# Clock2_1.net
KiCad netlist of a schematic drawn in EAGLE
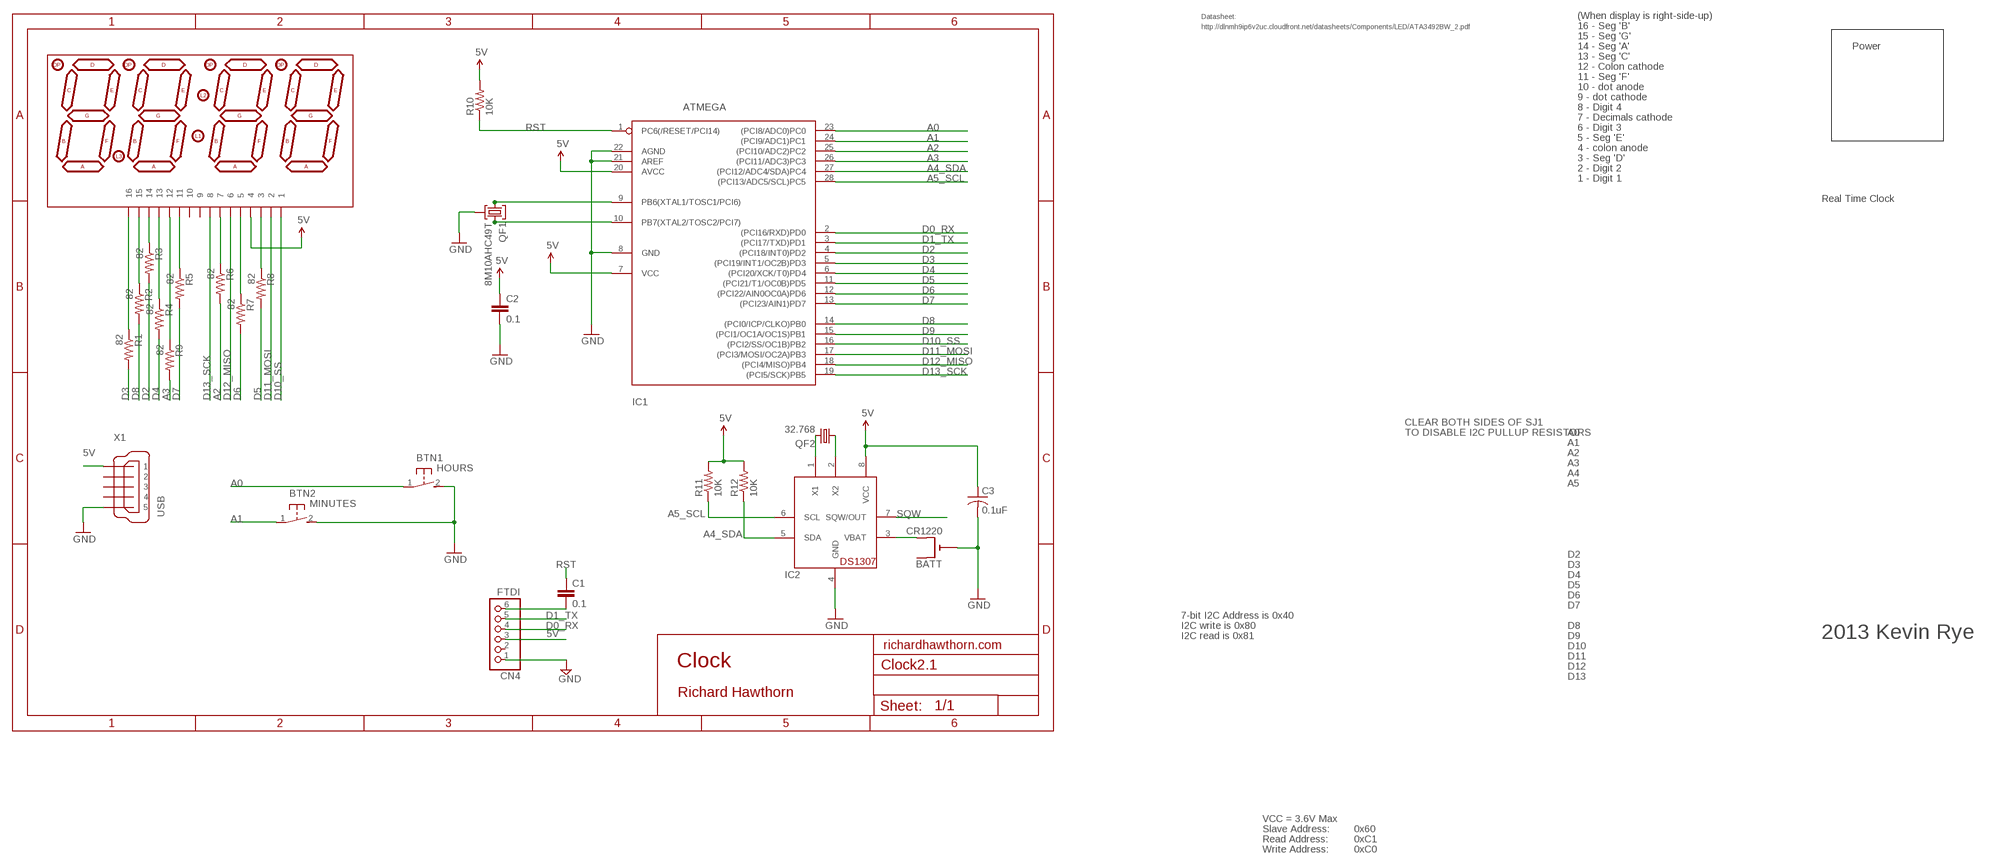
[diagram p0: schematic, sheet 1]

(export (version "E")
  (design (tool "Eeschema 10.0.6"))
  (components
    (comp (ref "BATT")
      (value "CR1220")
      (footprint "eagle-import:CR1220-SMD")
      (libsource (lib "eagle-import") (part "CR1220SMT"))
    )
    (comp (ref "BTN1")
      (value "HOURS")
      (footprint "eagle-import:DTS-3")
      (libsource (lib "eagle-import") (part "DTS-3"))
    )
    (comp (ref "BTN2")
      (value "MINUTES")
      (footprint "eagle-import:DTS-3")
      (libsource (lib "eagle-import") (part "DTS-3"))
    )
    (comp (ref "C1")
      (value "0.1")
      (footprint "eagle-import:CAP-PTH-SMALL2")
      (libsource (lib "eagle-import") (part "CAPPTH2"))
    )
    (comp (ref "C2")
      (value "0.1")
      (footprint "eagle-import:CAP-PTH-SMALL2")
      (libsource (lib "eagle-import") (part "CAPPTH2"))
    )
    (comp (ref "C3")
      (value "0.1uF")
      (footprint "eagle-import:C025-025X050")
      (libsource (lib "eagle-import") (part "C-US025-025X050"))
    )
    (comp (ref "CN4")
      (value "FTDI")
      (footprint "eagle-import:1X06")
      (libsource (lib "eagle-import") (part "PINHD-1X6"))
    )
    (comp (ref "IC1")
      (value "ATMEGA")
      (footprint "eagle-import:DIL28-3-ROUND")
      (libsource (lib "eagle-import") (part "ATMEGA168PROUND"))
    )
    (comp (ref "IC2")
      (value "DS1307")
      (footprint "eagle-import:DIL08")
      (libsource (lib "eagle-import") (part "DS1307"))
    )
    (comp (ref "LED1")
      (value "7SEG-4DIGIT")
      (footprint "eagle-import:SPARKFUN_7-SEGMENT-4DIGIT")
      (libsource (lib "eagle-import") (part "7SEG-4DIGIT"))
    )
    (comp (ref "QF1")
      (value "8M10AHC49T")
      (footprint "eagle-import:HC49U")
      (libsource (lib "eagle-import") (part "8M10AHC49T"))
    )
    (comp (ref "QF2")
      (value "32.768")
      (footprint "eagle-import:TC38H")
      (libsource (lib "eagle-import") (part "CRYTALTC38H"))
    )
    (comp (ref "R1")
      (value "82")
      (footprint "eagle-import:0204_7")
      (libsource (lib "eagle-import") (part "R-US_0204/7"))
    )
    (comp (ref "R2")
      (value "82")
      (footprint "eagle-import:0204_7")
      (libsource (lib "eagle-import") (part "R-US_0204/7"))
    )
    (comp (ref "R3")
      (value "82")
      (footprint "eagle-import:0204_7")
      (libsource (lib "eagle-import") (part "R-US_0204/7"))
    )
    (comp (ref "R4")
      (value "82")
      (footprint "eagle-import:0204_7")
      (libsource (lib "eagle-import") (part "R-US_0204/7"))
    )
    (comp (ref "R5")
      (value "82")
      (footprint "eagle-import:0204_7")
      (libsource (lib "eagle-import") (part "R-US_0204/7"))
    )
    (comp (ref "R6")
      (value "82")
      (footprint "eagle-import:0204_7")
      (libsource (lib "eagle-import") (part "R-US_0204/7"))
    )
    (comp (ref "R7")
      (value "82")
      (footprint "eagle-import:0204_7")
      (libsource (lib "eagle-import") (part "R-US_0204/7"))
    )
    (comp (ref "R8")
      (value "82")
      (footprint "eagle-import:0204_7")
      (libsource (lib "eagle-import") (part "R-US_0204/7"))
    )
    (comp (ref "R9")
      (value "82")
      (footprint "eagle-import:0204_7")
      (libsource (lib "eagle-import") (part "R-US_0204/7"))
    )
    (comp (ref "R10")
      (value "10K")
      (footprint "eagle-import:0204_7")
      (libsource (lib "eagle-import") (part "R-US_0204/7"))
    )
    (comp (ref "R11")
      (value "10K")
      (footprint "eagle-import:0204_7")
      (libsource (lib "eagle-import") (part "R-US_0204/7"))
    )
    (comp (ref "R12")
      (value "10K")
      (footprint "eagle-import:0204_7")
      (libsource (lib "eagle-import") (part "R-US_0204/7"))
    )
    (comp (ref "X1")
      (value "USB")
      (footprint "eagle-import:32005-601")
      (libsource (lib "eagle-import") (part "MINI-USB_SHIELD5P2-32005-601"))
    )
  )
  (nets
    (net (code "1") (name "/A0") (class "Default")
      (node (ref "BTN1") (pin "1") (pinfunction "1_1") (pintype "passive"))
      (node (ref "IC1") (pin "23") (pinfunction "(PCI8/ADC0)PC0_23") (pintype "bidirectional"))
    )
    (net (code "2") (name "/A1") (class "Default")
      (node (ref "BTN2") (pin "1") (pinfunction "1_1") (pintype "passive"))
      (node (ref "IC1") (pin "24") (pinfunction "(PCI9/ADC1)PC1_24") (pintype "bidirectional"))
    )
    (net (code "3") (name "/A2") (class "Default")
      (node (ref "IC1") (pin "25") (pinfunction "(PCI10/ADC2)PC2_25") (pintype "bidirectional"))
      (node (ref "R6") (pin "2") (pinfunction "2_2") (pintype "passive"))
    )
    (net (code "4") (name "/A3") (class "Default")
      (node (ref "IC1") (pin "26") (pinfunction "(PCI11/ADC3)PC3_26") (pintype "bidirectional"))
      (node (ref "R9") (pin "2") (pinfunction "2_2") (pintype "passive"))
    )
    (net (code "5") (name "/A4_SDA") (class "Default")
      (node (ref "IC1") (pin "27") (pinfunction "(PCI12/ADC4/SDA)PC4_27") (pintype "bidirectional"))
      (node (ref "IC2") (pin "5") (pinfunction "SDA_5") (pintype "bidirectional"))
      (node (ref "R12") (pin "1") (pinfunction "1_1") (pintype "passive"))
    )
    (net (code "6") (name "/A5_SCL") (class "Default")
      (node (ref "IC1") (pin "28") (pinfunction "(PCI13/ADC5/SCL)PC5_28") (pintype "bidirectional"))
      (node (ref "IC2") (pin "6") (pinfunction "SCL_6") (pintype "bidirectional"))
      (node (ref "R11") (pin "1") (pinfunction "1_1") (pintype "passive"))
    )
    (net (code "7") (name "/D0_RX") (class "Default")
      (node (ref "CN4") (pin "4") (pinfunction "4_4") (pintype "passive"))
      (node (ref "IC1") (pin "2") (pinfunction "(PCI16/RXD)PD0_2") (pintype "bidirectional"))
    )
    (net (code "8") (name "/D1_TX") (class "Default")
      (node (ref "CN4") (pin "5") (pinfunction "5_5") (pintype "passive"))
      (node (ref "IC1") (pin "3") (pinfunction "(PCI17/TXD)PD1_3") (pintype "bidirectional"))
    )
    (net (code "9") (name "/D2") (class "Default")
      (node (ref "IC1") (pin "4") (pinfunction "(PCI18/INT0)PD2_4") (pintype "bidirectional"))
      (node (ref "R3") (pin "2") (pinfunction "2_2") (pintype "passive"))
    )
    (net (code "10") (name "/D3") (class "Default")
      (node (ref "IC1") (pin "5") (pinfunction "(PCI19/INT1/OC2B)PD3_5") (pintype "bidirectional"))
      (node (ref "R1") (pin "2") (pinfunction "2_2") (pintype "passive"))
    )
    (net (code "11") (name "/D4") (class "Default")
      (node (ref "IC1") (pin "6") (pinfunction "(PCI20/XCK/T0)PD4_6") (pintype "bidirectional"))
      (node (ref "R4") (pin "2") (pinfunction "2_2") (pintype "passive"))
    )
    (net (code "12") (name "/D5") (class "Default")
      (node (ref "IC1") (pin "11") (pinfunction "(PCI21/T1/OC0B)PD5_11") (pintype "bidirectional"))
      (node (ref "R8") (pin "2") (pinfunction "2_2") (pintype "passive"))
    )
    (net (code "13") (name "/D6") (class "Default")
      (node (ref "IC1") (pin "12") (pinfunction "(PCI22/AIN0OC0A)PD6_12") (pintype "bidirectional"))
      (node (ref "R7") (pin "2") (pinfunction "2_2") (pintype "passive"))
    )
    (net (code "14") (name "/D7") (class "Default")
      (node (ref "IC1") (pin "13") (pinfunction "(PCI23/AIN1)PD7_13") (pintype "bidirectional"))
      (node (ref "R5") (pin "2") (pinfunction "2_2") (pintype "passive"))
    )
    (net (code "15") (name "/D8") (class "Default")
      (node (ref "IC1") (pin "14") (pinfunction "(PCI0/ICP/CLKO)PB0_14") (pintype "bidirectional"))
      (node (ref "R2") (pin "2") (pinfunction "2_2") (pintype "passive"))
    )
    (net (code "16") (name "/D9") (class "Default")
      (node (ref "IC1") (pin "15") (pinfunction "(PCI1/OC1A/OC1S)PB1_15") (pintype "bidirectional"))
    )
    (net (code "17") (name "/D10_SS") (class "Default")
      (node (ref "IC1") (pin "16") (pinfunction "(PCI2/SS/OC1B)PB2_16") (pintype "bidirectional"))
      (node (ref "LED1") (pin "1") (pinfunction "1_1") (pintype "bidirectional"))
    )
    (net (code "18") (name "/D11_MOSI") (class "Default")
      (node (ref "IC1") (pin "17") (pinfunction "(PCI3/MOSI/OC2A)PB3_17") (pintype "bidirectional"))
      (node (ref "LED1") (pin "2") (pinfunction "2_2") (pintype "bidirectional"))
    )
    (net (code "19") (name "/D12_MISO") (class "Default")
      (node (ref "IC1") (pin "18") (pinfunction "(PCI4/MISO)PB4_18") (pintype "bidirectional"))
      (node (ref "LED1") (pin "6") (pinfunction "6_6") (pintype "bidirectional"))
    )
    (net (code "20") (name "/D13_SCK") (class "Default")
      (node (ref "IC1") (pin "19") (pinfunction "(PCI5/SCK)PB5_19") (pintype "bidirectional"))
      (node (ref "LED1") (pin "8") (pinfunction "8_8") (pintype "bidirectional"))
    )
    (net (code "21") (name "/RST") (class "Default")
      (node (ref "C1") (pin "1") (pinfunction "1_1") (pintype "passive"))
      (node (ref "IC1") (pin "1") (pinfunction "PC6(/RESET/PCI14)_1") (pintype "bidirectional"))
      (node (ref "R10") (pin "1") (pinfunction "1_1") (pintype "passive"))
    )
    (net (code "22") (name "/SQW") (class "Default")
      (node (ref "IC2") (pin "7") (pinfunction "SQW/OUT_7") (pintype "bidirectional"))
    )
    (net (code "23") (name "5V") (class "Default")
      (node (ref "C2") (pin "1") (pinfunction "1_1") (pintype "passive"))
      (node (ref "C3") (pin "1") (pinfunction "1_1") (pintype "passive"))
      (node (ref "CN4") (pin "3") (pinfunction "3_3") (pintype "passive"))
      (node (ref "IC1") (pin "20") (pinfunction "AVCC_20") (pintype "bidirectional"))
      (node (ref "IC1") (pin "7") (pinfunction "VCC_7") (pintype "bidirectional"))
      (node (ref "IC2") (pin "8") (pinfunction "VCC_8") (pintype "power_in"))
      (node (ref "LED1") (pin "4") (pinfunction "4_4") (pintype "bidirectional"))
      (node (ref "R10") (pin "2") (pinfunction "2_2") (pintype "passive"))
      (node (ref "R11") (pin "2") (pinfunction "2_2") (pintype "passive"))
      (node (ref "R12") (pin "2") (pinfunction "2_2") (pintype "passive"))
      (node (ref "X1") (pin "1") (pinfunction "1_1") (pintype "passive"))
    )
    (net (code "24") (name "GND") (class "Default")
      (node (ref "BATT") (pin "-") (pinfunction "-_-") (pintype "passive"))
      (node (ref "BTN1") (pin "2") (pinfunction "2_2") (pintype "passive"))
      (node (ref "BTN2") (pin "2") (pinfunction "2_2") (pintype "passive"))
      (node (ref "C2") (pin "2") (pinfunction "2_2") (pintype "passive"))
      (node (ref "C3") (pin "2") (pinfunction "2_2") (pintype "passive"))
      (node (ref "CN4") (pin "1") (pinfunction "1_1") (pintype "passive"))
      (node (ref "IC1") (pin "21") (pinfunction "AREF_21") (pintype "bidirectional"))
      (node (ref "IC1") (pin "22") (pinfunction "AGND_22") (pintype "bidirectional"))
      (node (ref "IC1") (pin "8") (pinfunction "GND_8") (pintype "bidirectional"))
      (node (ref "IC2") (pin "4") (pinfunction "GND_4") (pintype "power_in"))
      (node (ref "QF1") (pin "2") (pinfunction "2_2") (pintype "passive"))
      (node (ref "X1") (pin "5") (pinfunction "5_5") (pintype "passive"))
    )
    (net (code "25") (name "Net-(BATT-+1)") (class "Default")
      (node (ref "BATT") (pin "+$2") (pinfunction "+1_+$2") (pintype "passive"))
      (node (ref "IC2") (pin "3") (pinfunction "VBAT_3") (pintype "power_in"))
    )
    (net (code "26") (name "Net-(C1-Pad2)") (class "Default")
      (node (ref "C1") (pin "2") (pinfunction "2_2") (pintype "passive"))
      (node (ref "CN4") (pin "6") (pinfunction "6_6") (pintype "passive"))
    )
    (net (code "27") (name "Net-(IC1-PB6(XTAL1{slash}TOSC1{slash}PCI6))") (class "Default")
      (node (ref "IC1") (pin "9") (pinfunction "PB6(XTAL1/TOSC1/PCI6)_9") (pintype "bidirectional"))
      (node (ref "QF1") (pin "1") (pinfunction "1_1") (pintype "passive"))
    )
    (net (code "28") (name "Net-(IC1-PB7(XTAL2{slash}TOSC2{slash}PCI7))") (class "Default")
      (node (ref "IC1") (pin "10") (pinfunction "PB7(XTAL2/TOSC2/PCI7)_10") (pintype "bidirectional"))
      (node (ref "QF1") (pin "3") (pinfunction "3_3") (pintype "passive"))
    )
    (net (code "29") (name "Net-(IC2-X1)") (class "Default")
      (node (ref "IC2") (pin "1") (pinfunction "X1_1") (pintype "passive"))
      (node (ref "QF2") (pin "2") (pinfunction "2_2") (pintype "passive"))
    )
    (net (code "30") (name "Net-(IC2-X2)") (class "Default")
      (node (ref "IC2") (pin "2") (pinfunction "X2_2") (pintype "passive"))
      (node (ref "QF2") (pin "1") (pinfunction "1_1") (pintype "passive"))
    )
    (net (code "31") (name "Net-(LED1-Pad3)") (class "Default")
      (node (ref "LED1") (pin "3") (pinfunction "3_3") (pintype "bidirectional"))
      (node (ref "R8") (pin "1") (pinfunction "1_1") (pintype "passive"))
    )
    (net (code "32") (name "Net-(LED1-Pad5)") (class "Default")
      (node (ref "LED1") (pin "5") (pinfunction "5_5") (pintype "bidirectional"))
      (node (ref "R7") (pin "1") (pinfunction "1_1") (pintype "passive"))
    )
    (net (code "33") (name "Net-(LED1-Pad7)") (class "Default")
      (node (ref "LED1") (pin "7") (pinfunction "7_7") (pintype "bidirectional"))
      (node (ref "R6") (pin "1") (pinfunction "1_1") (pintype "passive"))
    )
    (net (code "34") (name "Net-(LED1-Pad11)") (class "Default")
      (node (ref "LED1") (pin "11") (pinfunction "11_11") (pintype "bidirectional"))
      (node (ref "R5") (pin "1") (pinfunction "1_1") (pintype "passive"))
    )
    (net (code "35") (name "Net-(LED1-Pad12)") (class "Default")
      (node (ref "LED1") (pin "12") (pinfunction "12_12") (pintype "bidirectional"))
      (node (ref "R9") (pin "1") (pinfunction "1_1") (pintype "passive"))
    )
    (net (code "36") (name "Net-(LED1-Pad13)") (class "Default")
      (node (ref "LED1") (pin "13") (pinfunction "13_13") (pintype "bidirectional"))
      (node (ref "R4") (pin "1") (pinfunction "1_1") (pintype "passive"))
    )
    (net (code "37") (name "Net-(LED1-Pad14)") (class "Default")
      (node (ref "LED1") (pin "14") (pinfunction "14_14") (pintype "bidirectional"))
      (node (ref "R3") (pin "1") (pinfunction "1_1") (pintype "passive"))
    )
    (net (code "38") (name "Net-(LED1-Pad15)") (class "Default")
      (node (ref "LED1") (pin "15") (pinfunction "15_15") (pintype "bidirectional"))
      (node (ref "R2") (pin "1") (pinfunction "1_1") (pintype "passive"))
    )
    (net (code "39") (name "Net-(LED1-Pad16)") (class "Default")
      (node (ref "LED1") (pin "16") (pinfunction "16_16") (pintype "bidirectional"))
      (node (ref "R1") (pin "1") (pinfunction "1_1") (pintype "passive"))
    )
    (net (code "40") (name "unconnected-(BATT-+-Pad+$1)") (class "Default")
      (node (ref "BATT") (pin "+$1") (pinfunction "+_+$1") (pintype "passive"))
    )
    (net (code "41") (name "unconnected-(CN4-Pad2)") (class "Default")
      (node (ref "CN4") (pin "2") (pinfunction "2_2") (pintype "passive"))
    )
    (net (code "42") (name "unconnected-(LED1-Pad9)") (class "Default")
      (node (ref "LED1") (pin "9") (pinfunction "9_9") (pintype "bidirectional"))
    )
    (net (code "43") (name "unconnected-(LED1-Pad10)") (class "Default")
      (node (ref "LED1") (pin "10") (pinfunction "10_10") (pintype "bidirectional"))
    )
    (net (code "44") (name "unconnected-(X1-Pad2)") (class "Default")
      (node (ref "X1") (pin "2") (pinfunction "2_2") (pintype "passive"))
    )
    (net (code "45") (name "unconnected-(X1-Pad3)") (class "Default")
      (node (ref "X1") (pin "3") (pinfunction "3_3") (pintype "passive"))
    )
    (net (code "46") (name "unconnected-(X1-Pad4)") (class "Default")
      (node (ref "X1") (pin "4") (pinfunction "4_4") (pintype "passive"))
    )
  )
)
